# nusense-power.net
KiCad netlist of a schematic drawn in Altium Designer
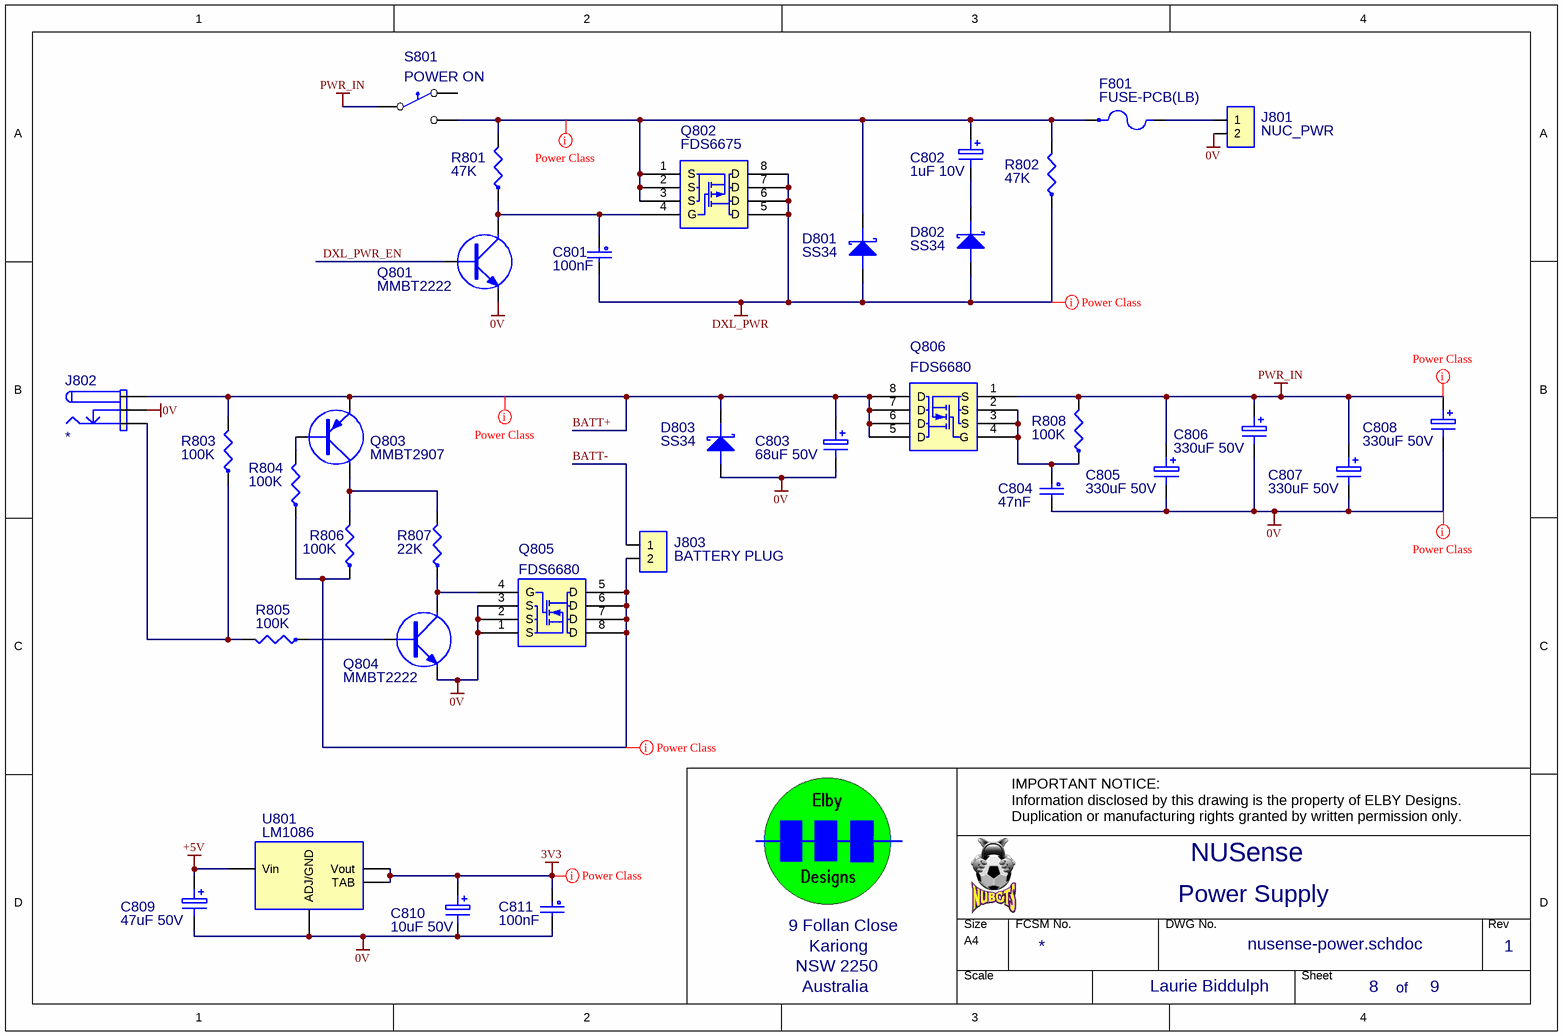
[diagram p0: nusense-power.schdoc]

(export (version "E")
  (design (tool "Eeschema 10.0.6"))
  (components
    (comp (ref "C801")
      (value "100nF")
      (footprint "RAD-0.2N(LB)")
      (description "Monolithic Ceramic")
      (libsource (lib "capacitor") (part "CC-100NF(LB)"))
    )
    (comp (ref "C802")
      (value "1uF 10V")
      (footprint "RB-D5.0-P2.0")
      (description "20% 50V Aluminium Electrolytic")
      (libsource (lib "capacitor") (part "CE-1UF50V(LB)"))
    )
    (comp (ref "C803")
      (value "68uF 50V")
      (footprint "RB-D6.3-P2.5")
      (description "20% 50V Aluminium Electrolytic")
      (libsource (lib "capacitor") (part "CE-68UF50V(LB)"))
    )
    (comp (ref "C804")
      (value "47nF")
      (footprint "RAD-0.2(LB)")
      (description "63V 10% Metallised Polyester")
      (libsource (lib "capacitor") (part "CP-47NF(LB)"))
    )
    (comp (ref "C805")
      (value "330uF 50V")
      (footprint "RB-D6.3-P2.5")
      (description "20% 50V Aluminium Electrolytic")
      (libsource (lib "capacitor") (part "CE-330UF50V(LB)"))
    )
    (comp (ref "C806")
      (value "330uF 50V")
      (footprint "RB-D6.3-P2.5")
      (description "20% 50V Aluminium Electrolytic")
      (libsource (lib "capacitor") (part "CE-330UF50V(LB)"))
    )
    (comp (ref "C807")
      (value "330uF 50V")
      (footprint "RB-D6.3-P2.5")
      (description "20% 50V Aluminium Electrolytic")
      (libsource (lib "capacitor") (part "CE-330UF50V(LB)"))
    )
    (comp (ref "C808")
      (value "330uF 50V")
      (footprint "RB-D6.3-P2.5")
      (description "20% 50V Aluminium Electrolytic")
      (libsource (lib "capacitor") (part "CE-330UF50V(LB)"))
    )
    (comp (ref "C809")
      (value "47uF 50V")
      (footprint "RB-D6.3-P2.5")
      (description "20% 50V Aluminium Electrolytic")
      (libsource (lib "capacitor") (part "CE-47UF50V(LB)"))
    )
    (comp (ref "C810")
      (value "10uF 50V")
      (footprint "RB-D6.3-P2.5")
      (description "20% 50V Aluminium Electrolytic")
      (libsource (lib "capacitor") (part "CE-10UF50V(LB)"))
    )
    (comp (ref "C811")
      (value "100nF")
      (footprint "RAD-0.2N(LB)")
      (description "Monolithic Ceramic")
      (libsource (lib "capacitor") (part "CC-100NF(LB)"))
    )
    (comp (ref "D801")
      (value "SS34")
      (footprint "DO-214AB (SMC)")
      (description "40V, 3A Sschottky Rectifier")
      (libsource (lib "semi") (part "SS34(LB)"))
    )
    (comp (ref "D802")
      (value "SS34")
      (footprint "DO-214AB (SMC)")
      (description "40V, 3A Sschottky Rectifier")
      (libsource (lib "semi") (part "SS34(LB)"))
    )
    (comp (ref "D803")
      (value "SS34")
      (footprint "DO-214AB (SMC)")
      (description "40V, 3A Sschottky Rectifier")
      (libsource (lib "semi") (part "SS34(LB)"))
    )
    (comp (ref "F801")
      (value "FUSE-PCB(LB)")
      (footprint "FUSE20MM(LB)")
      (description "PCB Fuse Holder and Fuse")
      (libsource (lib "passive") (part "FUSE-PCB(LB)"))
    )
    (comp (ref "J801")
      (value "NUC_PWR")
      (footprint "TERM254-2(LB)")
      (libsource (lib "connectors") (part "CON2(LB)"))
    )
    (comp (ref "J802")
      (value "*")
      (footprint "PCB-DC-SOCKET")
      (description "Switched 2.5mm DC Connector - PCB")
      (libsource (lib "connectors") (part "DC2.5MM-PCBV(LB)"))
    )
    (comp (ref "J803")
      (value "BATTERY PLUG")
      (footprint "TERM254-2(LB)")
      (libsource (lib "connectors") (part "CON2(LB)"))
    )
    (comp (ref "Q801")
      (value "MMBT2222")
      (footprint "SOT-23(LB)")
      (description "NPN Transistor")
      (libsource (lib "semi") (part "MMBT2222(SMD)"))
    )
    (comp (ref "Q802")
      (value "FDS6675")
      (footprint "SO-8")
      (description "40V P-Channel PowerTrench MOSFET")
      (libsource (lib "NuBots") (part "FDS6675"))
    )
    (comp (ref "Q803")
      (value "MMBT2907")
      (footprint "SOT-23(LB)")
      (description "PNP Transistor")
      (libsource (lib "semi") (part "MMBT2907(SMD)"))
    )
    (comp (ref "Q804")
      (value "MMBT2222")
      (footprint "SOT-23(LB)")
      (description "NPN Transistor")
      (libsource (lib "semi") (part "MMBT2222(SMD)"))
    )
    (comp (ref "Q805")
      (value "FDS6680")
      (footprint "SO-8")
      (description "30V N-Channel PowerTrench MOSFET")
      (libsource (lib "NuBots") (part "FDS6680"))
    )
    (comp (ref "Q806")
      (value "FDS6680")
      (footprint "SO-8")
      (description "30V N-Channel PowerTrench MOSFET")
      (libsource (lib "") (part "FDS6680_1"))
    )
    (comp (ref "R801")
      (value "47K")
      (footprint "AXIAL-0.4(LB)")
      (description "0.5W 1% Metal Film Resistor")
      (libsource (lib "resistor") (part "RM-47K(LB)"))
    )
    (comp (ref "R802")
      (value "47K")
      (footprint "AXIAL-0.4(LB)")
      (description "0.5W 1% Metal Film Resistor")
      (libsource (lib "resistor") (part "RM-47K(LB)"))
    )
    (comp (ref "R803")
      (value "100K")
      (footprint "AXIAL-0.4(LB)")
      (description "0.5W 1% Metal Film Resistor")
      (libsource (lib "resistor") (part "RM-100K(LB)"))
    )
    (comp (ref "R804")
      (value "100K")
      (footprint "AXIAL-0.4(LB)")
      (description "0.5W 1% Metal Film Resistor")
      (libsource (lib "resistor") (part "RM-100K(LB)"))
    )
    (comp (ref "R805")
      (value "100K")
      (footprint "AXIAL-0.4(LB)")
      (description "0.5W 1% Metal Film Resistor")
      (libsource (lib "resistor") (part "RM-100K(LB)"))
    )
    (comp (ref "R806")
      (value "100K")
      (footprint "AXIAL-0.4(LB)")
      (description "0.5W 1% Metal Film Resistor")
      (libsource (lib "resistor") (part "RM-100K(LB)"))
    )
    (comp (ref "R807")
      (value "22K")
      (footprint "AXIAL-0.4(LB)")
      (description "0.5W 1% Metal Film Resistor")
      (libsource (lib "resistor") (part "RM-22K(LB)"))
    )
    (comp (ref "R808")
      (value "100K")
      (footprint "AXIAL-0.4(LB)")
      (description "0.5W 1% Metal Film Resistor")
      (libsource (lib "resistor") (part "RM-100K(LB)"))
    )
    (comp (ref "S801")
      (value "POWER ON")
      (footprint "SW-SPDT-SLIDE-RA(LB)")
      (description "Single-pole, Double-throw Switch")
      (libsource (lib "switches") (part "SW-SPDT_11(LB)"))
    )
    (comp (ref "U801")
      (value "LM1086")
      (footprint "TO220-VHS-B(LB)")
      (description "3-terminal Positive Voltage Regulator")
      (libsource (lib "ic") (part "LM1086(LB)"))
    )
  )
  (nets
    (net (code "1") (name "+5V") (class "Default")
      (node (ref "C809") (pin "1") (pintype "passive"))
      (node (ref "U801") (pin "3") (pinfunction "Vin_3") (pintype "passive"))
    )
    (net (code "2") (name "/BATT+") (class "Default")
      (node (ref "C803") (pin "1") (pintype "passive"))
      (node (ref "D803") (pin "K") (pinfunction "K_K") (pintype "passive"))
      (node (ref "J802") (pin "1") (pinfunction "TIP_1") (pintype "power_in"))
      (node (ref "Q803") (pin "2") (pinfunction "E_2") (pintype "passive"))
      (node (ref "Q806") (pin "5") (pinfunction "D_5") (pintype "power_in"))
      (node (ref "Q806") (pin "6") (pinfunction "D_6") (pintype "power_in"))
      (node (ref "Q806") (pin "7") (pinfunction "D_7") (pintype "power_in"))
      (node (ref "Q806") (pin "8") (pinfunction "D_8") (pintype "power_in"))
      (node (ref "R803") (pin "2") (pinfunction "2_2") (pintype "passive"))
    )
    (net (code "3") (name "/BATT-") (class "Default")
      (node (ref "J803") (pin "1") (pinfunction "1_1") (pintype "passive"))
    )
    (net (code "4") (name "/DXL_PWR_EN") (class "Default")
      (node (ref "Q801") (pin "1") (pinfunction "B_1") (pintype "passive"))
    )
    (net (code "5") (name "0V") (class "Default")
      (node (ref "C803") (pin "2") (pintype "passive"))
      (node (ref "C804") (pin "2") (pintype "passive"))
      (node (ref "C805") (pin "2") (pintype "passive"))
      (node (ref "C806") (pin "2") (pintype "passive"))
      (node (ref "C807") (pin "2") (pintype "passive"))
      (node (ref "C808") (pin "2") (pintype "passive"))
      (node (ref "C809") (pin "2") (pintype "passive"))
      (node (ref "C810") (pin "2") (pintype "passive"))
      (node (ref "C811") (pin "2") (pintype "passive"))
      (node (ref "D803") (pin "A") (pinfunction "A_A") (pintype "passive"))
      (node (ref "J801") (pin "2") (pinfunction "2_2") (pintype "passive"))
      (node (ref "J802") (pin "2") (pinfunction "SWITCHED-BODY_2") (pintype "power_in"))
      (node (ref "Q801") (pin "2") (pinfunction "E_2") (pintype "passive"))
      (node (ref "Q804") (pin "2") (pinfunction "E_2") (pintype "passive"))
      (node (ref "Q805") (pin "1") (pinfunction "S_1") (pintype "power_in"))
      (node (ref "Q805") (pin "2") (pinfunction "S_2") (pintype "power_in"))
      (node (ref "Q805") (pin "3") (pinfunction "S_3") (pintype "power_in"))
      (node (ref "U801") (pin "1") (pinfunction "ADJ/GND_1") (pintype "passive"))
    )
    (net (code "6") (name "3V3") (class "Default")
      (node (ref "C810") (pin "1") (pintype "passive"))
      (node (ref "C811") (pin "1") (pintype "passive"))
      (node (ref "U801") (pin "2") (pinfunction "Vout_2") (pintype "passive"))
      (node (ref "U801") (pin "TAB") (pinfunction "TAB_TAB") (pintype "passive"))
    )
    (net (code "7") (name "DXL_PWR") (class "Default")
      (node (ref "C801") (pin "2") (pintype "passive"))
      (node (ref "D801") (pin "A") (pinfunction "A_A") (pintype "passive"))
      (node (ref "D802") (pin "A") (pinfunction "A_A") (pintype "passive"))
      (node (ref "Q802") (pin "5") (pinfunction "D_5") (pintype "power_in"))
      (node (ref "Q802") (pin "6") (pinfunction "D_6") (pintype "power_in"))
      (node (ref "Q802") (pin "7") (pinfunction "D_7") (pintype "power_in"))
      (node (ref "Q802") (pin "8") (pinfunction "D_8") (pintype "power_in"))
      (node (ref "R802") (pin "1") (pinfunction "1_1") (pintype "passive"))
    )
    (net (code "8") (name "Net-(C802-Pad2)") (class "Default")
      (node (ref "C802") (pin "2") (pintype "passive"))
      (node (ref "D802") (pin "K") (pinfunction "K_K") (pintype "passive"))
    )
    (net (code "9") (name "Net-(F801-Pad2)") (class "Default")
      (node (ref "F801") (pin "2") (pinfunction "2_2") (pintype "passive"))
      (node (ref "J801") (pin "1") (pinfunction "1_1") (pintype "passive"))
    )
    (net (code "10") (name "Net-(J802-Body)") (class "Default")
      (node (ref "J802") (pin "3") (pinfunction "Body_3") (pintype "power_in"))
      (node (ref "R803") (pin "1") (pinfunction "1_1") (pintype "passive"))
      (node (ref "R805") (pin "2") (pinfunction "2_2") (pintype "passive"))
    )
    (net (code "11") (name "Net-(J803-Pad2)") (class "Default")
      (node (ref "J803") (pin "2") (pinfunction "2_2") (pintype "passive"))
      (node (ref "Q805") (pin "5") (pinfunction "D_5") (pintype "power_in"))
      (node (ref "Q805") (pin "6") (pinfunction "D_6") (pintype "power_in"))
      (node (ref "Q805") (pin "7") (pinfunction "D_7") (pintype "power_in"))
      (node (ref "Q805") (pin "8") (pinfunction "D_8") (pintype "power_in"))
      (node (ref "R804") (pin "1") (pinfunction "1_1") (pintype "passive"))
      (node (ref "R806") (pin "1") (pinfunction "1_1") (pintype "passive"))
    )
    (net (code "12") (name "Net-(Q801-C)") (class "Default")
      (node (ref "C801") (pin "1") (pintype "passive"))
      (node (ref "Q801") (pin "3") (pinfunction "C_3") (pintype "passive"))
      (node (ref "Q802") (pin "4") (pinfunction "G_4") (pintype "power_in"))
      (node (ref "R801") (pin "1") (pinfunction "1_1") (pintype "passive"))
    )
    (net (code "13") (name "Net-(Q803-B)") (class "Default")
      (node (ref "Q803") (pin "1") (pinfunction "B_1") (pintype "passive"))
      (node (ref "R804") (pin "2") (pinfunction "2_2") (pintype "passive"))
    )
    (net (code "14") (name "Net-(Q803-C)") (class "Default")
      (node (ref "Q803") (pin "3") (pinfunction "C_3") (pintype "passive"))
      (node (ref "R806") (pin "2") (pinfunction "2_2") (pintype "passive"))
      (node (ref "R807") (pin "2") (pinfunction "2_2") (pintype "passive"))
    )
    (net (code "15") (name "Net-(Q804-B)") (class "Default")
      (node (ref "Q804") (pin "1") (pinfunction "B_1") (pintype "passive"))
      (node (ref "R805") (pin "1") (pinfunction "1_1") (pintype "passive"))
    )
    (net (code "16") (name "Net-(Q804-C)") (class "Default")
      (node (ref "Q804") (pin "3") (pinfunction "C_3") (pintype "passive"))
      (node (ref "Q805") (pin "4") (pinfunction "G_4") (pintype "power_in"))
      (node (ref "R807") (pin "1") (pinfunction "1_1") (pintype "passive"))
    )
    (net (code "17") (name "Net-(Q806-G)") (class "Default")
      (node (ref "C804") (pin "1") (pintype "passive"))
      (node (ref "Q806") (pin "2") (pinfunction "S_2") (pintype "power_in"))
      (node (ref "Q806") (pin "3") (pinfunction "S_3") (pintype "power_in"))
      (node (ref "Q806") (pin "4") (pinfunction "G_4") (pintype "power_in"))
      (node (ref "R808") (pin "1") (pinfunction "1_1") (pintype "passive"))
    )
    (net (code "18") (name "Net-(S801-NO)") (class "Default")
      (node (ref "C802") (pin "1") (pintype "passive"))
      (node (ref "D801") (pin "K") (pinfunction "K_K") (pintype "passive"))
      (node (ref "F801") (pin "1") (pinfunction "1_1") (pintype "passive"))
      (node (ref "Q802") (pin "1") (pinfunction "S_1") (pintype "power_in"))
      (node (ref "Q802") (pin "2") (pinfunction "S_2") (pintype "power_in"))
      (node (ref "Q802") (pin "3") (pinfunction "S_3") (pintype "power_in"))
      (node (ref "R801") (pin "2") (pinfunction "2_2") (pintype "passive"))
      (node (ref "R802") (pin "2") (pinfunction "2_2") (pintype "passive"))
      (node (ref "S801") (pin "2") (pinfunction "NO_2") (pintype "passive"))
    )
    (net (code "19") (name "PWR_IN") (class "Default")
      (node (ref "C805") (pin "1") (pintype "passive"))
      (node (ref "C806") (pin "1") (pintype "passive"))
      (node (ref "C807") (pin "1") (pintype "passive"))
      (node (ref "C808") (pin "1") (pintype "passive"))
      (node (ref "Q806") (pin "1") (pinfunction "S_1") (pintype "power_in"))
      (node (ref "R808") (pin "2") (pinfunction "2_2") (pintype "passive"))
      (node (ref "S801") (pin "1") (pinfunction "COM_1") (pintype "passive"))
    )
    (net (code "20") (name "unconnected-(S801-NC-Pad3)") (class "Default")
      (node (ref "S801") (pin "3") (pinfunction "NC_3") (pintype "passive"))
    )
  )
)
